# Motor_Driver_ClearanceIssues2.net
KiCad netlist of a schematic drawn in EAGLE
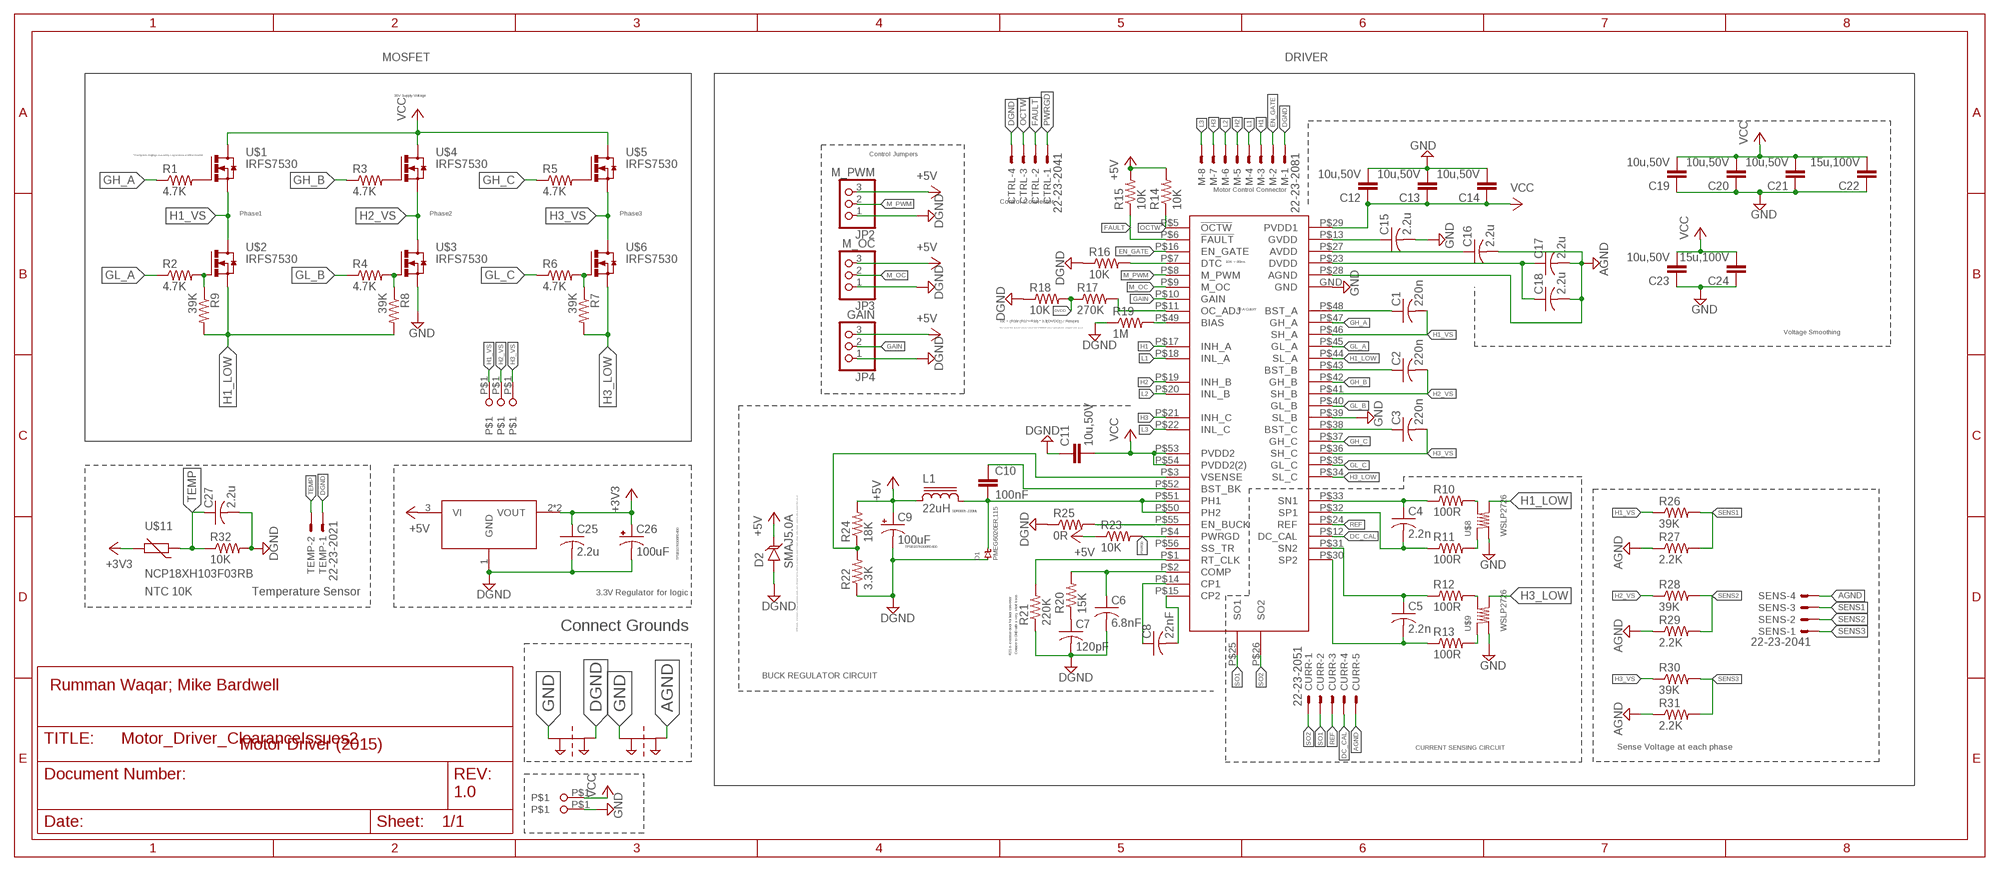
[diagram p0: schematic, sheet 1]

(export (version "E")
  (design (tool "Eeschema 10.0.6"))
  (components
    (comp (ref "C1")
      (value "220n")
      (footprint "eagle-import:C0805")
      (libsource (lib "eagle-import") (part "C-USC0805"))
    )
    (comp (ref "C2")
      (value "220n")
      (footprint "eagle-import:C0805")
      (libsource (lib "eagle-import") (part "C-USC0805"))
    )
    (comp (ref "C3")
      (value "220n")
      (footprint "eagle-import:C0805")
      (libsource (lib "eagle-import") (part "C-USC0805"))
    )
    (comp (ref "C4")
      (value "2.2n")
      (footprint "eagle-import:C0603")
      (libsource (lib "eagle-import") (part "C-USC0603"))
    )
    (comp (ref "C5")
      (value "2.2n")
      (footprint "eagle-import:C0603")
      (libsource (lib "eagle-import") (part "C-USC0603"))
    )
    (comp (ref "C6")
      (value "6.8nF")
      (footprint "eagle-import:C0603")
      (libsource (lib "eagle-import") (part "C-USC0603"))
    )
    (comp (ref "C7")
      (value "120pF")
      (footprint "eagle-import:C0603")
      (libsource (lib "eagle-import") (part "C-USC0603"))
    )
    (comp (ref "C8")
      (value "22nF")
      (footprint "eagle-import:C0603")
      (libsource (lib "eagle-import") (part "C-USC0603"))
    )
    (comp (ref "C9")
      (value "100uF")
      (footprint "eagle-import:EIA3528-KIT")
      (libsource (lib "eagle-import") (part "CAP_POL3528-KIT"))
    )
    (comp (ref "C10")
      (value "100nF")
      (footprint "eagle-import:0805")
      (libsource (lib "eagle-import") (part "CAP0805"))
    )
    (comp (ref "C11")
      (value "10u,50V")
      (footprint "eagle-import:1206")
      (libsource (lib "eagle-import") (part "CAP1206"))
    )
    (comp (ref "C12")
      (value "10u,50V")
      (footprint "eagle-import:1206")
      (libsource (lib "eagle-import") (part "CAP1206"))
    )
    (comp (ref "C13")
      (value "10u,50V")
      (footprint "eagle-import:1206")
      (libsource (lib "eagle-import") (part "CAP1206"))
    )
    (comp (ref "C14")
      (value "10u,50V")
      (footprint "eagle-import:1206")
      (libsource (lib "eagle-import") (part "CAP1206"))
    )
    (comp (ref "C15")
      (value "2.2u")
      (footprint "eagle-import:C0805")
      (libsource (lib "eagle-import") (part "C-USC0805"))
    )
    (comp (ref "C16")
      (value "2.2u")
      (footprint "eagle-import:C0805")
      (libsource (lib "eagle-import") (part "C-USC0805"))
    )
    (comp (ref "C17")
      (value "2.2u")
      (footprint "eagle-import:C0805")
      (libsource (lib "eagle-import") (part "C-USC0805"))
    )
    (comp (ref "C18")
      (value "2.2u")
      (footprint "eagle-import:C0805")
      (libsource (lib "eagle-import") (part "C-USC0805"))
    )
    (comp (ref "C19")
      (value "10u,50V")
      (footprint "eagle-import:1206")
      (libsource (lib "eagle-import") (part "CAP1206"))
    )
    (comp (ref "C20")
      (value "10u,50V")
      (footprint "eagle-import:1206")
      (libsource (lib "eagle-import") (part "CAP1206"))
    )
    (comp (ref "C21")
      (value "10u,50V")
      (footprint "eagle-import:1206")
      (libsource (lib "eagle-import") (part "CAP1206"))
    )
    (comp (ref "C22")
      (value "15u,100V")
      (footprint "eagle-import:C2220K")
      (libsource (lib "eagle-import") (part "C-EUC2220K"))
    )
    (comp (ref "C23")
      (value "10u,50V")
      (footprint "eagle-import:1206")
      (libsource (lib "eagle-import") (part "CAP1206"))
    )
    (comp (ref "C24")
      (value "15u,100V")
      (footprint "eagle-import:C2220K")
      (libsource (lib "eagle-import") (part "C-EUC2220K"))
    )
    (comp (ref "C25")
      (value "2.2u")
      (footprint "eagle-import:C0805")
      (libsource (lib "eagle-import") (part "C-USC0805"))
    )
    (comp (ref "C26")
      (value "100uF")
      (footprint "eagle-import:EIA3528-KIT")
      (libsource (lib "eagle-import") (part "CAP_POL3528-KIT"))
    )
    (comp (ref "C27")
      (value "2.2u")
      (footprint "eagle-import:C0805")
      (libsource (lib "eagle-import") (part "C-USC0805"))
    )
    (comp (ref "CTRL")
      (value "22-23-2041")
      (footprint "eagle-import:22-23-2041")
      (fields (field (name "MF") "MOLEX"))
      (libsource (lib "eagle-import") (part "22-23-2041"))
    )
    (comp (ref "CURR")
      (value "22-23-2051")
      (footprint "eagle-import:22-23-2051")
      (fields (field (name "MF") "MOLEX"))
      (libsource (lib "eagle-import") (part "22-23-2051"))
    )
    (comp (ref "D1")
      (value "PMEG6020ER,115")
      (footprint "eagle-import:SOD123W")
      (libsource (lib "eagle-import") (part "DIODE[SCHOTKY]-SOD123W"))
    )
    (comp (ref "D2")
      (value "SMAJ5.0A")
      (footprint "eagle-import:SMA-DIODE")
      (libsource (lib "eagle-import") (part "TVSSMA"))
    )
    (comp (ref "JP2")
      (value "M_PWM")
      (footprint "eagle-import:1X03")
      (libsource (lib "eagle-import") (part "PINHD-1X3"))
    )
    (comp (ref "JP3")
      (value "M_OC")
      (footprint "eagle-import:1X03")
      (libsource (lib "eagle-import") (part "PINHD-1X3"))
    )
    (comp (ref "JP4")
      (value "GAIN")
      (footprint "eagle-import:1X03")
      (libsource (lib "eagle-import") (part "PINHD-1X3"))
    )
    (comp (ref "L1")
      (value "22uH")
      (footprint "eagle-import:SDR0805")
      (libsource (lib "eagle-import") (part "SDR0805"))
    )
    (comp (ref "M")
      (value "22-23-2081")
      (footprint "eagle-import:22-23-2081")
      (fields (field (name "MF") "MOLEX"))
      (libsource (lib "eagle-import") (part "22-23-2081"))
    )
    (comp (ref "PT1")
      (value "2PT_GND_TIE")
      (footprint "eagle-import:2PT_GND_TIE")
      (libsource (lib "eagle-import") (part "2PT_GND_TIE"))
    )
    (comp (ref "PT2")
      (value "2PT_GND_TIE")
      (footprint "eagle-import:2PT_GND_TIE")
      (libsource (lib "eagle-import") (part "2PT_GND_TIE"))
    )
    (comp (ref "R1")
      (value "4.7K")
      (footprint "eagle-import:R0603")
      (libsource (lib "eagle-import") (part "R-US_R0603"))
    )
    (comp (ref "R2")
      (value "4.7K")
      (footprint "eagle-import:R0603")
      (libsource (lib "eagle-import") (part "R-US_R0603"))
    )
    (comp (ref "R3")
      (value "4.7K")
      (footprint "eagle-import:R0603")
      (libsource (lib "eagle-import") (part "R-US_R0603"))
    )
    (comp (ref "R4")
      (value "4.7K")
      (footprint "eagle-import:R0603")
      (libsource (lib "eagle-import") (part "R-US_R0603"))
    )
    (comp (ref "R5")
      (value "4.7K")
      (footprint "eagle-import:R0603")
      (libsource (lib "eagle-import") (part "R-US_R0603"))
    )
    (comp (ref "R6")
      (value "4.7K")
      (footprint "eagle-import:R0603")
      (libsource (lib "eagle-import") (part "R-US_R0603"))
    )
    (comp (ref "R7")
      (value "39K")
      (footprint "eagle-import:R0603")
      (libsource (lib "eagle-import") (part "R-US_R0603"))
    )
    (comp (ref "R8")
      (value "39K")
      (footprint "eagle-import:R0603")
      (libsource (lib "eagle-import") (part "R-US_R0603"))
    )
    (comp (ref "R9")
      (value "39K")
      (footprint "eagle-import:R0603")
      (libsource (lib "eagle-import") (part "R-US_R0603"))
    )
    (comp (ref "R10")
      (value "100R")
      (footprint "eagle-import:R0603")
      (libsource (lib "eagle-import") (part "R-US_R0603"))
    )
    (comp (ref "R11")
      (value "100R")
      (footprint "eagle-import:R0603")
      (libsource (lib "eagle-import") (part "R-US_R0603"))
    )
    (comp (ref "R12")
      (value "100R")
      (footprint "eagle-import:R0603")
      (libsource (lib "eagle-import") (part "R-US_R0603"))
    )
    (comp (ref "R13")
      (value "100R")
      (footprint "eagle-import:R0603")
      (libsource (lib "eagle-import") (part "R-US_R0603"))
    )
    (comp (ref "R14")
      (value "10K")
      (footprint "eagle-import:R0603")
      (libsource (lib "eagle-import") (part "R-US_R0603"))
    )
    (comp (ref "R15")
      (value "10K")
      (footprint "eagle-import:R0603")
      (libsource (lib "eagle-import") (part "R-US_R0603"))
    )
    (comp (ref "R16")
      (value "10K")
      (footprint "eagle-import:R0603")
      (libsource (lib "eagle-import") (part "R-US_R0603"))
    )
    (comp (ref "R17")
      (value "270K")
      (footprint "eagle-import:R0603")
      (libsource (lib "eagle-import") (part "R-US_R0603"))
    )
    (comp (ref "R18")
      (value "10K")
      (footprint "eagle-import:R0603")
      (libsource (lib "eagle-import") (part "R-US_R0603"))
    )
    (comp (ref "R19")
      (value "1M")
      (footprint "eagle-import:R0603")
      (libsource (lib "eagle-import") (part "R-US_R0603"))
    )
    (comp (ref "R20")
      (value "15K")
      (footprint "eagle-import:R0603")
      (libsource (lib "eagle-import") (part "R-US_R0603"))
    )
    (comp (ref "R21")
      (value "220K")
      (footprint "eagle-import:R0603")
      (libsource (lib "eagle-import") (part "R-US_R0603"))
    )
    (comp (ref "R22")
      (value "3.3K")
      (footprint "eagle-import:R0603")
      (libsource (lib "eagle-import") (part "R-US_R0603"))
    )
    (comp (ref "R23")
      (value "10K")
      (footprint "eagle-import:R0603")
      (libsource (lib "eagle-import") (part "R-US_R0603"))
    )
    (comp (ref "R24")
      (value "18K")
      (footprint "eagle-import:R0603")
      (libsource (lib "eagle-import") (part "R-US_R0603"))
    )
    (comp (ref "R25")
      (value "0R")
      (footprint "eagle-import:R0603")
      (libsource (lib "eagle-import") (part "R-US_R0603"))
    )
    (comp (ref "R26")
      (value "39K")
      (footprint "eagle-import:R0805")
      (libsource (lib "eagle-import") (part "R-US_R0805"))
    )
    (comp (ref "R27")
      (value "2.2K")
      (footprint "eagle-import:R0805")
      (libsource (lib "eagle-import") (part "R-US_R0805"))
    )
    (comp (ref "R28")
      (value "39K")
      (footprint "eagle-import:R0805")
      (libsource (lib "eagle-import") (part "R-US_R0805"))
    )
    (comp (ref "R29")
      (value "2.2K")
      (footprint "eagle-import:R0805")
      (libsource (lib "eagle-import") (part "R-US_R0805"))
    )
    (comp (ref "R30")
      (value "39K")
      (footprint "eagle-import:R0805")
      (libsource (lib "eagle-import") (part "R-US_R0805"))
    )
    (comp (ref "R31")
      (value "2.2K")
      (footprint "eagle-import:R0805")
      (libsource (lib "eagle-import") (part "R-US_R0805"))
    )
    (comp (ref "R32")
      (value "10K")
      (footprint "eagle-import:M0805")
      (libsource (lib "eagle-import") (part "R-US_M0805"))
    )
    (comp (ref "SENS")
      (value "22-23-2041")
      (footprint "eagle-import:22-23-2041")
      (fields (field (name "MF") "MOLEX"))
      (libsource (lib "eagle-import") (part "22-23-2041"))
    )
    (comp (ref "TEMP")
      (value "22-23-2021")
      (footprint "eagle-import:22-23-2021")
      (fields (field (name "MF") "MOLEX"))
      (libsource (lib "eagle-import") (part "22-23-2021"))
    )
    (comp (ref "U$1")
      (value "IRFS7530")
      (footprint "eagle-import:IRF7530_HEATSINK")
      (libsource (lib "eagle-import") (part "IRFS7530_HEATSINK"))
    )
    (comp (ref "U$2")
      (value "IRFS7530")
      (footprint "eagle-import:IRF7530_HEATSINK")
      (libsource (lib "eagle-import") (part "IRFS7530_HEATSINK"))
    )
    (comp (ref "U$3")
      (value "IRFS7530")
      (footprint "eagle-import:IRF7530_HEATSINK")
      (libsource (lib "eagle-import") (part "IRFS7530_HEATSINK"))
    )
    (comp (ref "U$4")
      (value "IRFS7530")
      (footprint "eagle-import:IRF7530_HEATSINK")
      (libsource (lib "eagle-import") (part "IRFS7530_HEATSINK"))
    )
    (comp (ref "U$5")
      (value "IRFS7530")
      (footprint "eagle-import:IRF7530_HEATSINK")
      (libsource (lib "eagle-import") (part "IRFS7530_HEATSINK"))
    )
    (comp (ref "U$6")
      (value "IRFS7530")
      (footprint "eagle-import:IRF7530_HEATSINK")
      (libsource (lib "eagle-import") (part "IRFS7530_HEATSINK"))
    )
    (comp (ref "U$7")
      (value "DRV8302")
      (footprint "eagle-import:DRV8302")
      (libsource (lib "eagle-import") (part "DRV8302"))
    )
    (comp (ref "U$8")
      (value "WSLP2726")
      (footprint "eagle-import:WSLP2726")
      (libsource (lib "eagle-import") (part "WSLP2726"))
    )
    (comp (ref "U$9")
      (value "WSLP2726")
      (footprint "eagle-import:WSLP2726")
      (libsource (lib "eagle-import") (part "WSLP2726"))
    )
    (comp (ref "U$10")
      (value "TC2117")
      (footprint "eagle-import:SOT223")
      (libsource (lib "eagle-import") (part "TC2117"))
    )
    (comp (ref "U$11")
      (value "NCP18XH103F03RB")
      (footprint "eagle-import:R0603")
      (libsource (lib "eagle-import") (part "NCP18XH103F03RB"))
    )
    (comp (ref "U$12")
      (value "1CONN_SOLDER")
      (footprint "eagle-import:1CONN_PAD")
      (libsource (lib "eagle-import") (part "1CONN_SOLDER"))
    )
    (comp (ref "U$13")
      (value "1CONN_SOLDER")
      (footprint "eagle-import:1CONN_PAD")
      (libsource (lib "eagle-import") (part "1CONN_SOLDER"))
    )
    (comp (ref "U$14")
      (value "1CONN_SOLDER")
      (footprint "eagle-import:1CONN_PAD")
      (libsource (lib "eagle-import") (part "1CONN_SOLDER"))
    )
    (comp (ref "U$15")
      (value "1CONN_SOLDER")
      (footprint "eagle-import:1CONN_PAD")
      (libsource (lib "eagle-import") (part "1CONN_SOLDER"))
    )
    (comp (ref "U$16")
      (value "1CONN_SOLDER")
      (footprint "eagle-import:1CONN_PAD")
      (libsource (lib "eagle-import") (part "1CONN_SOLDER"))
    )
  )
  (nets
    (net (code "1") (name "+3V3") (class "Default")
      (node (ref "C25") (pin "1") (pinfunction "1_1") (pintype "passive"))
      (node (ref "C26") (pin "A") (pinfunction "+_A") (pintype "passive"))
      (node (ref "U$10") (pin "2") (pinfunction "VOUT_2") (pintype "bidirectional"))
      (node (ref "U$10") (pin "4") (pinfunction "VOUT_4") (pintype "bidirectional"))
      (node (ref "U$11") (pin "2") (pinfunction "2_2") (pintype "passive"))
    )
    (net (code "2") (name "+5V") (class "Default")
      (node (ref "C9") (pin "A") (pinfunction "+_A") (pintype "passive"))
      (node (ref "D2") (pin "C") (pinfunction "C_C") (pintype "passive"))
      (node (ref "JP2") (pin "3") (pinfunction "3_3") (pintype "passive"))
      (node (ref "JP3") (pin "3") (pinfunction "3_3") (pintype "passive"))
      (node (ref "JP4") (pin "3") (pinfunction "3_3") (pintype "passive"))
      (node (ref "L1") (pin "1") (pinfunction "1_1") (pintype "passive"))
      (node (ref "R14") (pin "2") (pinfunction "2_2") (pintype "passive"))
      (node (ref "R15") (pin "2") (pinfunction "2_2") (pintype "passive"))
      (node (ref "R23") (pin "1") (pinfunction "1_1") (pintype "passive"))
      (node (ref "R24") (pin "2") (pinfunction "2_2") (pintype "passive"))
      (node (ref "U$10") (pin "3") (pinfunction "VI_3") (pintype "bidirectional"))
    )
    (net (code "3") (name "AGND") (class "Default")
      (node (ref "C16") (pin "2") (pinfunction "2_2") (pintype "passive"))
      (node (ref "C17") (pin "2") (pinfunction "2_2") (pintype "passive"))
      (node (ref "C18") (pin "2") (pinfunction "2_2") (pintype "passive"))
      (node (ref "CURR") (pin "5") (pinfunction "S_5") (pintype "passive"))
      (node (ref "PT2") (pin "P$2") (pinfunction "P$2_P$2") (pintype "bidirectional"))
      (node (ref "R27") (pin "1") (pinfunction "1_1") (pintype "passive"))
      (node (ref "R29") (pin "1") (pinfunction "1_1") (pintype "passive"))
      (node (ref "R31") (pin "1") (pinfunction "1_1") (pintype "passive"))
      (node (ref "SENS") (pin "4") (pinfunction "S_4") (pintype "passive"))
      (node (ref "U$7") (pin "P$28") (pinfunction "AGND_P$28") (pintype "bidirectional"))
    )
    (net (code "4") (name "DC_CAL") (class "Default")
      (node (ref "CURR") (pin "4") (pinfunction "S_4") (pintype "passive"))
      (node (ref "U$7") (pin "P$12") (pinfunction "DC_CAL_P$12") (pintype "bidirectional"))
    )
    (net (code "5") (name "DGND") (class "Default")
      (node (ref "C11") (pin "1") (pinfunction "1_1") (pintype "passive"))
      (node (ref "C25") (pin "2") (pinfunction "2_2") (pintype "passive"))
      (node (ref "C26") (pin "C") (pinfunction "-_C") (pintype "passive"))
      (node (ref "C27") (pin "2") (pinfunction "2_2") (pintype "passive"))
      (node (ref "C6") (pin "2") (pinfunction "2_2") (pintype "passive"))
      (node (ref "C7") (pin "2") (pinfunction "2_2") (pintype "passive"))
      (node (ref "C9") (pin "C") (pinfunction "-_C") (pintype "passive"))
      (node (ref "CTRL") (pin "4") (pinfunction "S_4") (pintype "passive"))
      (node (ref "D1") (pin "P$1") (pinfunction "1_P$1") (pintype "bidirectional"))
      (node (ref "D2") (pin "A") (pinfunction "A_A") (pintype "passive"))
      (node (ref "JP2") (pin "1") (pinfunction "1_1") (pintype "passive"))
      (node (ref "JP3") (pin "1") (pinfunction "1_1") (pintype "passive"))
      (node (ref "JP4") (pin "1") (pinfunction "1_1") (pintype "passive"))
      (node (ref "M") (pin "1") (pinfunction "S_1") (pintype "passive"))
      (node (ref "PT1") (pin "P$2") (pinfunction "P$2_P$2") (pintype "bidirectional"))
      (node (ref "R16") (pin "1") (pinfunction "1_1") (pintype "passive"))
      (node (ref "R18") (pin "1") (pinfunction "1_1") (pintype "passive"))
      (node (ref "R19") (pin "1") (pinfunction "1_1") (pintype "passive"))
      (node (ref "R21") (pin "1") (pinfunction "1_1") (pintype "passive"))
      (node (ref "R22") (pin "1") (pinfunction "1_1") (pintype "passive"))
      (node (ref "R25") (pin "1") (pinfunction "1_1") (pintype "passive"))
      (node (ref "R32") (pin "2") (pinfunction "2_2") (pintype "passive"))
      (node (ref "TEMP") (pin "1") (pinfunction "S_1") (pintype "passive"))
      (node (ref "U$10") (pin "1") (pinfunction "GND_1") (pintype "bidirectional"))
    )
    (net (code "6") (name "DVDD") (class "Default")
      (node (ref "R17") (pin "1") (pinfunction "1_1") (pintype "passive"))
      (node (ref "R18") (pin "2") (pinfunction "2_2") (pintype "passive"))
    )
    (net (code "7") (name "EN_GATE") (class "Default")
      (node (ref "M") (pin "2") (pinfunction "S_2") (pintype "passive"))
      (node (ref "U$7") (pin "P$16") (pinfunction "EN_GATE_P$16") (pintype "bidirectional"))
    )
    (net (code "8") (name "FAULT") (class "Default")
      (node (ref "CTRL") (pin "2") (pinfunction "S_2") (pintype "passive"))
      (node (ref "R15") (pin "1") (pinfunction "1_1") (pintype "passive"))
      (node (ref "U$7") (pin "P$6") (pinfunction "~{FAULT}_P$6") (pintype "bidirectional"))
    )
    (net (code "9") (name "GAIN") (class "Default")
      (node (ref "JP4") (pin "2") (pinfunction "2_2") (pintype "passive"))
      (node (ref "U$7") (pin "P$10") (pinfunction "GAIN_P$10") (pintype "bidirectional"))
    )
    (net (code "10") (name "GH_A") (class "Default")
      (node (ref "R1") (pin "1") (pinfunction "1_1") (pintype "passive"))
      (node (ref "U$7") (pin "P$47") (pinfunction "GH_A_P$47") (pintype "bidirectional"))
    )
    (net (code "11") (name "GH_B") (class "Default")
      (node (ref "R3") (pin "1") (pinfunction "1_1") (pintype "passive"))
      (node (ref "U$7") (pin "P$42") (pinfunction "GH_B_P$42") (pintype "bidirectional"))
    )
    (net (code "12") (name "GH_C") (class "Default")
      (node (ref "R5") (pin "1") (pinfunction "1_1") (pintype "passive"))
      (node (ref "U$7") (pin "P$37") (pinfunction "GH_C_P$37") (pintype "bidirectional"))
    )
    (net (code "13") (name "GL_A") (class "Default")
      (node (ref "R2") (pin "1") (pinfunction "1_1") (pintype "passive"))
      (node (ref "U$7") (pin "P$45") (pinfunction "GL_A_P$45") (pintype "bidirectional"))
    )
    (net (code "14") (name "GL_B") (class "Default")
      (node (ref "R4") (pin "1") (pinfunction "1_1") (pintype "passive"))
      (node (ref "U$7") (pin "P$40") (pinfunction "GL_B_P$40") (pintype "bidirectional"))
    )
    (net (code "15") (name "GL_C") (class "Default")
      (node (ref "R6") (pin "1") (pinfunction "1_1") (pintype "passive"))
      (node (ref "U$7") (pin "P$35") (pinfunction "GL_C_P$35") (pintype "bidirectional"))
    )
    (net (code "16") (name "GND") (class "Default")
      (node (ref "C12") (pin "2") (pinfunction "2_2") (pintype "passive"))
      (node (ref "C13") (pin "2") (pinfunction "2_2") (pintype "passive"))
      (node (ref "C14") (pin "2") (pinfunction "2_2") (pintype "passive"))
      (node (ref "C15") (pin "2") (pinfunction "2_2") (pintype "passive"))
      (node (ref "C19") (pin "1") (pinfunction "1_1") (pintype "passive"))
      (node (ref "C20") (pin "1") (pinfunction "1_1") (pintype "passive"))
      (node (ref "C21") (pin "1") (pinfunction "1_1") (pintype "passive"))
      (node (ref "C22") (pin "1") (pinfunction "1_1") (pintype "passive"))
      (node (ref "C23") (pin "1") (pinfunction "1_1") (pintype "passive"))
      (node (ref "C24") (pin "1") (pinfunction "1_1") (pintype "passive"))
      (node (ref "PT1") (pin "P$1") (pinfunction "P$1_P$1") (pintype "bidirectional"))
      (node (ref "PT2") (pin "P$1") (pinfunction "P$1_P$1") (pintype "bidirectional"))
      (node (ref "U$16") (pin "P$1") (pinfunction "P$1_P$1") (pintype "bidirectional"))
      (node (ref "U$3") (pin "S1") (pinfunction "S_S1") (pintype "passive"))
      (node (ref "U$3") (pin "S2") (pinfunction "S_S2") (pintype "passive"))
      (node (ref "U$3") (pin "S3") (pinfunction "S_S3") (pintype "passive"))
      (node (ref "U$3") (pin "S4") (pinfunction "S_S4") (pintype "passive"))
      (node (ref "U$3") (pin "S5") (pinfunction "S_S5") (pintype "passive"))
      (node (ref "U$7") (pin "GND") (pinfunction "GND_GND") (pintype "bidirectional"))
      (node (ref "U$7") (pin "P$39") (pinfunction "SL_B_P$39") (pintype "bidirectional"))
      (node (ref "U$8") (pin "P$2") (pinfunction "P$2_P$2") (pintype "bidirectional"))
      (node (ref "U$9") (pin "P$2") (pinfunction "P$2_P$2") (pintype "bidirectional"))
    )
    (net (code "17") (name "H1") (class "Default")
      (node (ref "M") (pin "3") (pinfunction "S_3") (pintype "passive"))
      (node (ref "U$7") (pin "P$17") (pinfunction "INH_A_P$17") (pintype "bidirectional"))
    )
    (net (code "18") (name "H1_LOW") (class "Default")
      (node (ref "R8") (pin "2") (pinfunction "2_2") (pintype "passive"))
      (node (ref "R9") (pin "2") (pinfunction "2_2") (pintype "passive"))
      (node (ref "U$2") (pin "S1") (pinfunction "S_S1") (pintype "passive"))
      (node (ref "U$2") (pin "S2") (pinfunction "S_S2") (pintype "passive"))
      (node (ref "U$2") (pin "S3") (pinfunction "S_S3") (pintype "passive"))
      (node (ref "U$2") (pin "S4") (pinfunction "S_S4") (pintype "passive"))
      (node (ref "U$2") (pin "S5") (pinfunction "S_S5") (pintype "passive"))
      (node (ref "U$7") (pin "P$44") (pinfunction "SL_A_P$44") (pintype "bidirectional"))
      (node (ref "U$8") (pin "P$1") (pinfunction "P$1_P$1") (pintype "bidirectional"))
    )
    (net (code "19") (name "H1_VS") (class "Default")
      (node (ref "C1") (pin "2") (pinfunction "2_2") (pintype "passive"))
      (node (ref "R26") (pin "1") (pinfunction "1_1") (pintype "passive"))
      (node (ref "U$1") (pin "S1") (pinfunction "S_S1") (pintype "passive"))
      (node (ref "U$1") (pin "S2") (pinfunction "S_S2") (pintype "passive"))
      (node (ref "U$1") (pin "S3") (pinfunction "S_S3") (pintype "passive"))
      (node (ref "U$1") (pin "S4") (pinfunction "S_S4") (pintype "passive"))
      (node (ref "U$1") (pin "S5") (pinfunction "S_S5") (pintype "passive"))
      (node (ref "U$14") (pin "P$1") (pinfunction "P$1_P$1") (pintype "bidirectional"))
      (node (ref "U$2") (pin "D1") (pinfunction "D_D1") (pintype "passive"))
      (node (ref "U$7") (pin "P$46") (pinfunction "SH_A_P$46") (pintype "bidirectional"))
    )
    (net (code "20") (name "H2") (class "Default")
      (node (ref "M") (pin "5") (pinfunction "S_5") (pintype "passive"))
      (node (ref "U$7") (pin "P$19") (pinfunction "INH_B_P$19") (pintype "bidirectional"))
    )
    (net (code "21") (name "H2_VS") (class "Default")
      (node (ref "C2") (pin "2") (pinfunction "2_2") (pintype "passive"))
      (node (ref "R28") (pin "1") (pinfunction "1_1") (pintype "passive"))
      (node (ref "U$13") (pin "P$1") (pinfunction "P$1_P$1") (pintype "bidirectional"))
      (node (ref "U$3") (pin "D1") (pinfunction "D_D1") (pintype "passive"))
      (node (ref "U$4") (pin "S1") (pinfunction "S_S1") (pintype "passive"))
      (node (ref "U$4") (pin "S2") (pinfunction "S_S2") (pintype "passive"))
      (node (ref "U$4") (pin "S3") (pinfunction "S_S3") (pintype "passive"))
      (node (ref "U$4") (pin "S4") (pinfunction "S_S4") (pintype "passive"))
      (node (ref "U$4") (pin "S5") (pinfunction "S_S5") (pintype "passive"))
      (node (ref "U$7") (pin "P$41") (pinfunction "SH_B_P$41") (pintype "bidirectional"))
    )
    (net (code "22") (name "H3") (class "Default")
      (node (ref "M") (pin "7") (pinfunction "S_7") (pintype "passive"))
      (node (ref "U$7") (pin "P$21") (pinfunction "INH_C_P$21") (pintype "bidirectional"))
    )
    (net (code "23") (name "H3_LOW") (class "Default")
      (node (ref "R7") (pin "2") (pinfunction "2_2") (pintype "passive"))
      (node (ref "U$6") (pin "S1") (pinfunction "S_S1") (pintype "passive"))
      (node (ref "U$6") (pin "S2") (pinfunction "S_S2") (pintype "passive"))
      (node (ref "U$6") (pin "S3") (pinfunction "S_S3") (pintype "passive"))
      (node (ref "U$6") (pin "S4") (pinfunction "S_S4") (pintype "passive"))
      (node (ref "U$6") (pin "S5") (pinfunction "S_S5") (pintype "passive"))
      (node (ref "U$7") (pin "P$34") (pinfunction "SL_C_P$34") (pintype "bidirectional"))
      (node (ref "U$9") (pin "P$1") (pinfunction "P$1_P$1") (pintype "bidirectional"))
    )
    (net (code "24") (name "H3_VS") (class "Default")
      (node (ref "C3") (pin "2") (pinfunction "2_2") (pintype "passive"))
      (node (ref "R30") (pin "1") (pinfunction "1_1") (pintype "passive"))
      (node (ref "U$12") (pin "P$1") (pinfunction "P$1_P$1") (pintype "bidirectional"))
      (node (ref "U$5") (pin "S1") (pinfunction "S_S1") (pintype "passive"))
      (node (ref "U$5") (pin "S2") (pinfunction "S_S2") (pintype "passive"))
      (node (ref "U$5") (pin "S3") (pinfunction "S_S3") (pintype "passive"))
      (node (ref "U$5") (pin "S4") (pinfunction "S_S4") (pintype "passive"))
      (node (ref "U$5") (pin "S5") (pinfunction "S_S5") (pintype "passive"))
      (node (ref "U$6") (pin "D1") (pinfunction "D_D1") (pintype "passive"))
      (node (ref "U$7") (pin "P$36") (pinfunction "SH_C_P$36") (pintype "bidirectional"))
    )
    (net (code "25") (name "L1") (class "Default")
      (node (ref "M") (pin "4") (pinfunction "S_4") (pintype "passive"))
      (node (ref "U$7") (pin "P$18") (pinfunction "INL_A_P$18") (pintype "bidirectional"))
    )
    (net (code "26") (name "L2") (class "Default")
      (node (ref "M") (pin "6") (pinfunction "S_6") (pintype "passive"))
      (node (ref "U$7") (pin "P$20") (pinfunction "INL_B_P$20") (pintype "bidirectional"))
    )
    (net (code "27") (name "L3") (class "Default")
      (node (ref "M") (pin "8") (pinfunction "S_8") (pintype "passive"))
      (node (ref "U$7") (pin "P$22") (pinfunction "INL_C_P$22") (pintype "bidirectional"))
    )
    (net (code "28") (name "M_OC") (class "Default")
      (node (ref "JP3") (pin "2") (pinfunction "2_2") (pintype "passive"))
      (node (ref "U$7") (pin "P$9") (pinfunction "M_OC_P$9") (pintype "bidirectional"))
    )
    (net (code "29") (name "M_PWM") (class "Default")
      (node (ref "JP2") (pin "2") (pinfunction "2_2") (pintype "passive"))
      (node (ref "U$7") (pin "P$8") (pinfunction "M_PWM_P$8") (pintype "bidirectional"))
    )
    (net (code "30") (name "Net-(C7-Pad1)") (class "Default")
      (node (ref "C7") (pin "1") (pinfunction "1_1") (pintype "passive"))
      (node (ref "R20") (pin "1") (pinfunction "1_1") (pintype "passive"))
    )
    (net (code "31") (name "Net-(D1-2)") (class "Default")
      (node (ref "C10") (pin "2") (pinfunction "2_2") (pintype "passive"))
      (node (ref "D1") (pin "P$2") (pinfunction "2_P$2") (pintype "bidirectional"))
      (node (ref "L1") (pin "2") (pinfunction "2_2") (pintype "passive"))
      (node (ref "U$7") (pin "P$50") (pinfunction "PH2_P$50") (pintype "bidirectional"))
      (node (ref "U$7") (pin "P$51") (pinfunction "PH1_P$51") (pintype "bidirectional"))
    )
    (net (code "32") (name "Net-(R10-Pad2)") (class "Default")
      (node (ref "R10") (pin "2") (pinfunction "2_2") (pintype "passive"))
      (node (ref "U$8") (pin "P$3") (pinfunction "P$3_P$3") (pintype "bidirectional"))
    )
    (net (code "33") (name "Net-(R11-Pad2)") (class "Default")
      (node (ref "R11") (pin "2") (pinfunction "2_2") (pintype "passive"))
      (node (ref "U$8") (pin "P$4") (pinfunction "P$4_P$4") (pintype "bidirectional"))
    )
    (net (code "34") (name "Net-(R12-Pad2)") (class "Default")
      (node (ref "R12") (pin "2") (pinfunction "2_2") (pintype "passive"))
      (node (ref "U$9") (pin "P$3") (pinfunction "P$3_P$3") (pintype "bidirectional"))
    )
    (net (code "35") (name "Net-(R13-Pad2)") (class "Default")
      (node (ref "R13") (pin "2") (pinfunction "2_2") (pintype "passive"))
      (node (ref "U$9") (pin "P$4") (pinfunction "P$4_P$4") (pintype "bidirectional"))
    )
    (net (code "36") (name "Net-(U$1-G)") (class "Default")
      (node (ref "R1") (pin "2") (pinfunction "2_2") (pintype "passive"))
      (node (ref "U$1") (pin "G1") (pinfunction "G_G1") (pintype "passive"))
    )
    (net (code "37") (name "Net-(U$2-G)") (class "Default")
      (node (ref "R2") (pin "2") (pinfunction "2_2") (pintype "passive"))
      (node (ref "R9") (pin "1") (pinfunction "1_1") (pintype "passive"))
      (node (ref "U$2") (pin "G1") (pinfunction "G_G1") (pintype "passive"))
    )
    (net (code "38") (name "Net-(U$3-G)") (class "Default")
      (node (ref "R4") (pin "2") (pinfunction "2_2") (pintype "passive"))
      (node (ref "R8") (pin "1") (pinfunction "1_1") (pintype "passive"))
      (node (ref "U$3") (pin "G1") (pinfunction "G_G1") (pintype "passive"))
    )
    (net (code "39") (name "Net-(U$4-G)") (class "Default")
      (node (ref "R3") (pin "2") (pinfunction "2_2") (pintype "passive"))
      (node (ref "U$4") (pin "G1") (pinfunction "G_G1") (pintype "passive"))
    )
    (net (code "40") (name "Net-(U$5-G)") (class "Default")
      (node (ref "R5") (pin "2") (pinfunction "2_2") (pintype "passive"))
      (node (ref "U$5") (pin "G1") (pinfunction "G_G1") (pintype "passive"))
    )
    (net (code "41") (name "Net-(U$6-G)") (class "Default")
      (node (ref "R6") (pin "2") (pinfunction "2_2") (pintype "passive"))
      (node (ref "R7") (pin "1") (pinfunction "1_1") (pintype "passive"))
      (node (ref "U$6") (pin "G1") (pinfunction "G_G1") (pintype "passive"))
    )
    (net (code "42") (name "Net-(U$7-AVDD)") (class "Default")
      (node (ref "C16") (pin "1") (pinfunction "1_1") (pintype "passive"))
      (node (ref "U$7") (pin "P$27") (pinfunction "AVDD_P$27") (pintype "bidirectional"))
    )
    (net (code "43") (name "Net-(U$7-BIAS)") (class "Default")
      (node (ref "R19") (pin "2") (pinfunction "2_2") (pintype "passive"))
      (node (ref "U$7") (pin "P$49") (pinfunction "BIAS_P$49") (pintype "bidirectional"))
    )
    (net (code "44") (name "Net-(U$7-BST_A)") (class "Default")
      (node (ref "C1") (pin "1") (pinfunction "1_1") (pintype "passive"))
      (node (ref "U$7") (pin "P$48") (pinfunction "BST_A_P$48") (pintype "bidirectional"))
    )
    (net (code "45") (name "Net-(U$7-BST_B)") (class "Default")
      (node (ref "C2") (pin "1") (pinfunction "1_1") (pintype "passive"))
      (node (ref "U$7") (pin "P$43") (pinfunction "BST_B_P$43") (pintype "bidirectional"))
    )
    (net (code "46") (name "Net-(U$7-BST_BK)") (class "Default")
      (node (ref "C10") (pin "1") (pinfunction "1_1") (pintype "passive"))
      (node (ref "U$7") (pin "P$52") (pinfunction "BST_BK_P$52") (pintype "bidirectional"))
    )
    (net (code "47") (name "Net-(U$7-BST_C)") (class "Default")
      (node (ref "C3") (pin "1") (pinfunction "1_1") (pintype "passive"))
      (node (ref "U$7") (pin "P$38") (pinfunction "BST_C_P$38") (pintype "bidirectional"))
    )
    (net (code "48") (name "Net-(U$7-COMP)") (class "Default")
      (node (ref "C6") (pin "1") (pinfunction "1_1") (pintype "passive"))
      (node (ref "R20") (pin "2") (pinfunction "2_2") (pintype "passive"))
      (node (ref "U$7") (pin "P$2") (pinfunction "COMP_P$2") (pintype "bidirectional"))
    )
    (net (code "49") (name "Net-(U$7-CP1)") (class "Default")
      (node (ref "C8") (pin "1") (pinfunction "1_1") (pintype "passive"))
      (node (ref "U$7") (pin "P$14") (pinfunction "CP1_P$14") (pintype "bidirectional"))
    )
    (net (code "50") (name "Net-(U$7-CP2)") (class "Default")
      (node (ref "C8") (pin "2") (pinfunction "2_2") (pintype "passive"))
      (node (ref "U$7") (pin "P$15") (pinfunction "CP2_P$15") (pintype "bidirectional"))
    )
    (net (code "51") (name "Net-(U$7-DTC)") (class "Default")
      (node (ref "R16") (pin "2") (pinfunction "2_2") (pintype "passive"))
      (node (ref "U$7") (pin "P$7") (pinfunction "DTC_P$7") (pintype "bidirectional"))
    )
    (net (code "52") (name "Net-(U$7-DVDD)") (class "Default")
      (node (ref "C17") (pin "1") (pinfunction "1_1") (pintype "passive"))
      (node (ref "C18") (pin "1") (pinfunction "1_1") (pintype "passive"))
      (node (ref "U$7") (pin "P$23") (pinfunction "DVDD_P$23") (pintype "bidirectional"))
    )
    (net (code "53") (name "Net-(U$7-EN_BUCK)") (class "Default")
      (node (ref "R25") (pin "2") (pinfunction "2_2") (pintype "passive"))
      (node (ref "U$7") (pin "P$55") (pinfunction "EN_BUCK_P$55") (pintype "bidirectional"))
    )
    (net (code "54") (name "Net-(U$7-GVDD)") (class "Default")
      (node (ref "C15") (pin "1") (pinfunction "1_1") (pintype "passive"))
      (node (ref "U$7") (pin "P$13") (pinfunction "GVDD_P$13") (pintype "bidirectional"))
    )
    (net (code "55") (name "Net-(U$7-OC_ADJ)") (class "Default")
      (node (ref "R17") (pin "2") (pinfunction "2_2") (pintype "passive"))
      (node (ref "U$7") (pin "P$11") (pinfunction "OC_ADJ_P$11") (pintype "bidirectional"))
    )
    (net (code "56") (name "Net-(U$7-RT_CLK)") (class "Default")
      (node (ref "R21") (pin "2") (pinfunction "2_2") (pintype "passive"))
      (node (ref "U$7") (pin "P$1") (pinfunction "RT_CLK_P$1") (pintype "bidirectional"))
    )
    (net (code "57") (name "Net-(U$7-SN1)") (class "Default")
      (node (ref "C4") (pin "1") (pinfunction "1_1") (pintype "passive"))
      (node (ref "R10") (pin "1") (pinfunction "1_1") (pintype "passive"))
      (node (ref "U$7") (pin "P$33") (pinfunction "SN1_P$33") (pintype "bidirectional"))
    )
    (net (code "58") (name "Net-(U$7-SN2)") (class "Default")
      (node (ref "C5") (pin "1") (pinfunction "1_1") (pintype "passive"))
      (node (ref "R12") (pin "1") (pinfunction "1_1") (pintype "passive"))
      (node (ref "U$7") (pin "P$31") (pinfunction "SN2_P$31") (pintype "bidirectional"))
    )
    (net (code "59") (name "Net-(U$7-SP1)") (class "Default")
      (node (ref "C4") (pin "2") (pinfunction "2_2") (pintype "passive"))
      (node (ref "R11") (pin "1") (pinfunction "1_1") (pintype "passive"))
      (node (ref "U$7") (pin "P$32") (pinfunction "SP1_P$32") (pintype "bidirectional"))
    )
    (net (code "60") (name "Net-(U$7-SP2)") (class "Default")
      (node (ref "C5") (pin "2") (pinfunction "2_2") (pintype "passive"))
      (node (ref "R13") (pin "1") (pinfunction "1_1") (pintype "passive"))
      (node (ref "U$7") (pin "P$30") (pinfunction "SP2_P$30") (pintype "bidirectional"))
    )
    (net (code "61") (name "Net-(U$7-VSENSE)") (class "Default")
      (node (ref "R22") (pin "2") (pinfunction "2_2") (pintype "passive"))
      (node (ref "R24") (pin "1") (pinfunction "1_1") (pintype "passive"))
      (node (ref "U$7") (pin "P$3") (pinfunction "VSENSE_P$3") (pintype "bidirectional"))
    )
    (net (code "62") (name "OCTW") (class "Default")
      (node (ref "CTRL") (pin "3") (pinfunction "S_3") (pintype "passive"))
      (node (ref "R14") (pin "1") (pinfunction "1_1") (pintype "passive"))
      (node (ref "U$7") (pin "P$5") (pinfunction "~{OCTW}_P$5") (pintype "bidirectional"))
    )
    (net (code "63") (name "PWRGD") (class "Default")
      (node (ref "CTRL") (pin "1") (pinfunction "S_1") (pintype "passive"))
      (node (ref "R23") (pin "2") (pinfunction "2_2") (pintype "passive"))
      (node (ref "U$7") (pin "P$4") (pinfunction "PWRGD_P$4") (pintype "bidirectional"))
    )
    (net (code "64") (name "REF") (class "Default")
      (node (ref "CURR") (pin "3") (pinfunction "S_3") (pintype "passive"))
      (node (ref "U$7") (pin "P$24") (pinfunction "REF_P$24") (pintype "bidirectional"))
    )
    (net (code "65") (name "SENS1") (class "Default")
      (node (ref "R26") (pin "2") (pinfunction "2_2") (pintype "passive"))
      (node (ref "R27") (pin "2") (pinfunction "2_2") (pintype "passive"))
      (node (ref "SENS") (pin "3") (pinfunction "S_3") (pintype "passive"))
    )
    (net (code "66") (name "SENS2") (class "Default")
      (node (ref "R28") (pin "2") (pinfunction "2_2") (pintype "passive"))
      (node (ref "R29") (pin "2") (pinfunction "2_2") (pintype "passive"))
      (node (ref "SENS") (pin "2") (pinfunction "S_2") (pintype "passive"))
    )
    (net (code "67") (name "SENS3") (class "Default")
      (node (ref "R30") (pin "2") (pinfunction "2_2") (pintype "passive"))
      (node (ref "R31") (pin "2") (pinfunction "2_2") (pintype "passive"))
      (node (ref "SENS") (pin "1") (pinfunction "S_1") (pintype "passive"))
    )
    (net (code "68") (name "SO1") (class "Default")
      (node (ref "CURR") (pin "2") (pinfunction "S_2") (pintype "passive"))
      (node (ref "U$7") (pin "P$25") (pinfunction "SO1_P$25") (pintype "bidirectional"))
    )
    (net (code "69") (name "SO2") (class "Default")
      (node (ref "CURR") (pin "1") (pinfunction "S_1") (pintype "passive"))
      (node (ref "U$7") (pin "P$26") (pinfunction "SO2_P$26") (pintype "bidirectional"))
    )
    (net (code "70") (name "TEMP") (class "Default")
      (node (ref "C27") (pin "1") (pinfunction "1_1") (pintype "passive"))
      (node (ref "R32") (pin "1") (pinfunction "1_1") (pintype "passive"))
      (node (ref "TEMP") (pin "2") (pinfunction "S_2") (pintype "passive"))
      (node (ref "U$11") (pin "1") (pinfunction "1_1") (pintype "passive"))
    )
    (net (code "71") (name "VCC") (class "Default")
      (node (ref "C11") (pin "2") (pinfunction "2_2") (pintype "passive"))
      (node (ref "C12") (pin "1") (pinfunction "1_1") (pintype "passive"))
      (node (ref "C13") (pin "1") (pinfunction "1_1") (pintype "passive"))
      (node (ref "C14") (pin "1") (pinfunction "1_1") (pintype "passive"))
      (node (ref "C19") (pin "2") (pinfunction "2_2") (pintype "passive"))
      (node (ref "C20") (pin "2") (pinfunction "2_2") (pintype "passive"))
      (node (ref "C21") (pin "2") (pinfunction "2_2") (pintype "passive"))
      (node (ref "C22") (pin "2") (pinfunction "2_2") (pintype "passive"))
      (node (ref "C23") (pin "2") (pinfunction "2_2") (pintype "passive"))
      (node (ref "C24") (pin "2") (pinfunction "2_2") (pintype "passive"))
      (node (ref "U$1") (pin "D1") (pinfunction "D_D1") (pintype "passive"))
      (node (ref "U$15") (pin "P$1") (pinfunction "P$1_P$1") (pintype "bidirectional"))
      (node (ref "U$4") (pin "D1") (pinfunction "D_D1") (pintype "passive"))
      (node (ref "U$5") (pin "D1") (pinfunction "D_D1") (pintype "passive"))
      (node (ref "U$7") (pin "P$29") (pinfunction "PVDD1_P$29") (pintype "bidirectional"))
      (node (ref "U$7") (pin "P$53") (pinfunction "PVDD2_P$53") (pintype "bidirectional"))
      (node (ref "U$7") (pin "P$54") (pinfunction "PVDD2(2)_P$54") (pintype "bidirectional"))
    )
    (net (code "72") (name "unconnected-(U$7-SS_TR-PadP$56)") (class "Default")
      (node (ref "U$7") (pin "P$56") (pinfunction "SS_TR_P$56") (pintype "bidirectional"))
    )
  )
)
